# GucciAux.net
KiCad netlist of a schematic drawn in EAGLE
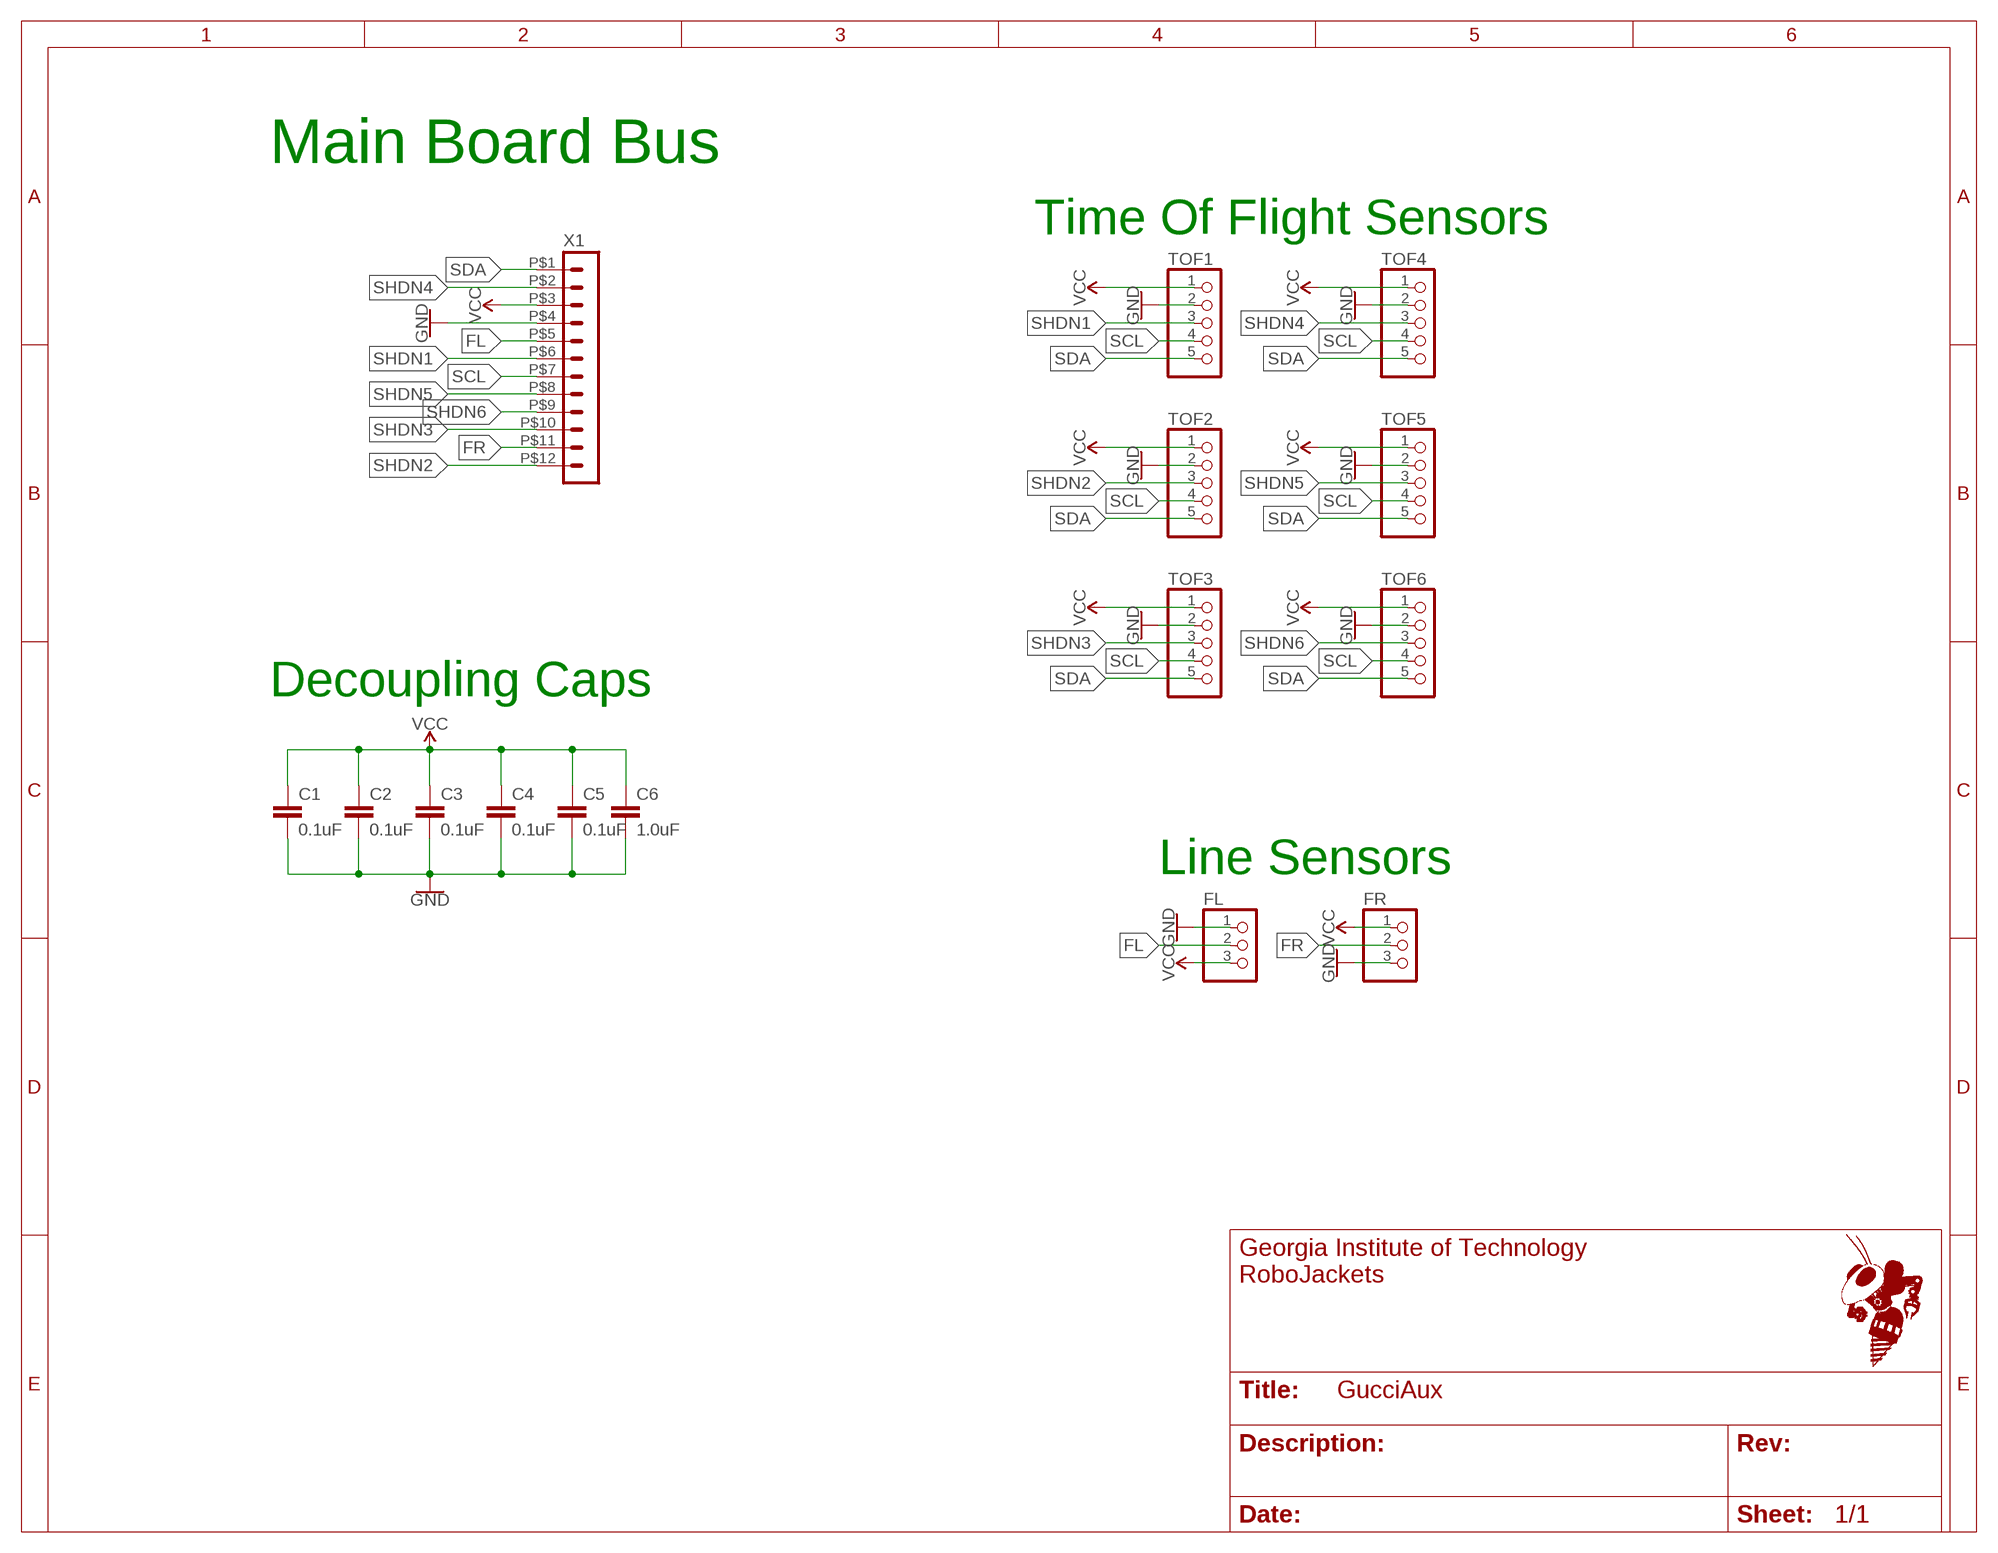
[diagram p0: schematic, sheet 1]

(export (version "E")
  (design (tool "Eeschema 10.0.6"))
  (components
    (comp (ref "C1")
      (value "0.1uF")
      (footprint "eagle-import:0603")
      (libsource (lib "eagle-import") (part "0.1UF-0603-25V-(+80/-20%)"))
    )
    (comp (ref "C2")
      (value "0.1uF")
      (footprint "eagle-import:0603")
      (libsource (lib "eagle-import") (part "0.1UF-0603-25V-(+80/-20%)"))
    )
    (comp (ref "C3")
      (value "0.1uF")
      (footprint "eagle-import:0603")
      (libsource (lib "eagle-import") (part "0.1UF-0603-25V-(+80/-20%)"))
    )
    (comp (ref "C4")
      (value "0.1uF")
      (footprint "eagle-import:0603")
      (libsource (lib "eagle-import") (part "0.1UF-0603-25V-(+80/-20%)"))
    )
    (comp (ref "C5")
      (value "0.1uF")
      (footprint "eagle-import:0603")
      (libsource (lib "eagle-import") (part "0.1UF-0603-25V-(+80/-20%)"))
    )
    (comp (ref "C6")
      (value "1.0uF")
      (footprint "eagle-import:0603")
      (libsource (lib "eagle-import") (part "1.0UF-0603-16V-10%"))
    )
    (comp (ref "FL")
      (value "PINHD-1X3")
      (footprint "eagle-import:1X03")
      (libsource (lib "eagle-import") (part "PINHD-1X3"))
    )
    (comp (ref "FR")
      (value "PINHD-1X3")
      (footprint "eagle-import:1X03")
      (libsource (lib "eagle-import") (part "PINHD-1X3"))
    )
    (comp (ref "TOF1")
      (value "PINHD-1X5")
      (footprint "eagle-import:1X05")
      (libsource (lib "eagle-import") (part "PINHD-1X5"))
    )
    (comp (ref "TOF2")
      (value "PINHD-1X5")
      (footprint "eagle-import:1X05")
      (libsource (lib "eagle-import") (part "PINHD-1X5"))
    )
    (comp (ref "TOF3")
      (value "PINHD-1X5")
      (footprint "eagle-import:1X05")
      (libsource (lib "eagle-import") (part "PINHD-1X5"))
    )
    (comp (ref "TOF4")
      (value "PINHD-1X5")
      (footprint "eagle-import:1X05")
      (libsource (lib "eagle-import") (part "PINHD-1X5"))
    )
    (comp (ref "TOF5")
      (value "PINHD-1X5")
      (footprint "eagle-import:1X05")
      (libsource (lib "eagle-import") (part "PINHD-1X5"))
    )
    (comp (ref "TOF6")
      (value "PINHD-1X5")
      (footprint "eagle-import:1X05")
      (libsource (lib "eagle-import") (part "PINHD-1X5"))
    )
    (comp (ref "X1")
      (value "HEADER_POS12_43045-1212")
      (footprint "eagle-import:43045-1212")
      (libsource (lib "eagle-import") (part "HEADER_POS12_?43045-1212"))
    )
  )
  (nets
    (net (code "1") (name "FL") (class "Default")
      (node (ref "FL") (pin "2") (pinfunction "2_2") (pintype "passive"))
      (node (ref "X1") (pin "P$5") (pinfunction "5_P$5") (pintype "passive"))
    )
    (net (code "2") (name "FR") (class "Default")
      (node (ref "FR") (pin "2") (pinfunction "2_2") (pintype "passive"))
      (node (ref "X1") (pin "P$11") (pinfunction "11_P$11") (pintype "passive"))
    )
    (net (code "3") (name "GND") (class "Default")
      (node (ref "C1") (pin "2") (pinfunction "2_2") (pintype "passive"))
      (node (ref "C2") (pin "2") (pinfunction "2_2") (pintype "passive"))
      (node (ref "C3") (pin "2") (pinfunction "2_2") (pintype "passive"))
      (node (ref "C4") (pin "2") (pinfunction "2_2") (pintype "passive"))
      (node (ref "C5") (pin "2") (pinfunction "2_2") (pintype "passive"))
      (node (ref "C6") (pin "2") (pinfunction "2_2") (pintype "passive"))
      (node (ref "FL") (pin "1") (pinfunction "1_1") (pintype "passive"))
      (node (ref "FR") (pin "3") (pinfunction "3_3") (pintype "passive"))
      (node (ref "TOF1") (pin "2") (pinfunction "2_2") (pintype "passive"))
      (node (ref "TOF2") (pin "2") (pinfunction "2_2") (pintype "passive"))
      (node (ref "TOF3") (pin "2") (pinfunction "2_2") (pintype "passive"))
      (node (ref "TOF4") (pin "2") (pinfunction "2_2") (pintype "passive"))
      (node (ref "TOF5") (pin "2") (pinfunction "2_2") (pintype "passive"))
      (node (ref "TOF6") (pin "2") (pinfunction "2_2") (pintype "passive"))
      (node (ref "X1") (pin "P$4") (pinfunction "4_P$4") (pintype "passive"))
    )
    (net (code "4") (name "SCL") (class "Default")
      (node (ref "TOF1") (pin "4") (pinfunction "4_4") (pintype "passive"))
      (node (ref "TOF2") (pin "4") (pinfunction "4_4") (pintype "passive"))
      (node (ref "TOF3") (pin "4") (pinfunction "4_4") (pintype "passive"))
      (node (ref "TOF4") (pin "4") (pinfunction "4_4") (pintype "passive"))
      (node (ref "TOF5") (pin "4") (pinfunction "4_4") (pintype "passive"))
      (node (ref "TOF6") (pin "4") (pinfunction "4_4") (pintype "passive"))
      (node (ref "X1") (pin "P$7") (pinfunction "7_P$7") (pintype "passive"))
    )
    (net (code "5") (name "SDA") (class "Default")
      (node (ref "TOF1") (pin "5") (pinfunction "5_5") (pintype "passive"))
      (node (ref "TOF2") (pin "5") (pinfunction "5_5") (pintype "passive"))
      (node (ref "TOF3") (pin "5") (pinfunction "5_5") (pintype "passive"))
      (node (ref "TOF4") (pin "5") (pinfunction "5_5") (pintype "passive"))
      (node (ref "TOF5") (pin "5") (pinfunction "5_5") (pintype "passive"))
      (node (ref "TOF6") (pin "5") (pinfunction "5_5") (pintype "passive"))
      (node (ref "X1") (pin "P$1") (pinfunction "1_P$1") (pintype "passive"))
    )
    (net (code "6") (name "SHDN1") (class "Default")
      (node (ref "TOF1") (pin "3") (pinfunction "3_3") (pintype "passive"))
      (node (ref "X1") (pin "P$6") (pinfunction "6_P$6") (pintype "passive"))
    )
    (net (code "7") (name "SHDN2") (class "Default")
      (node (ref "TOF2") (pin "3") (pinfunction "3_3") (pintype "passive"))
      (node (ref "X1") (pin "P$12") (pinfunction "12_P$12") (pintype "passive"))
    )
    (net (code "8") (name "SHDN3") (class "Default")
      (node (ref "TOF3") (pin "3") (pinfunction "3_3") (pintype "passive"))
      (node (ref "X1") (pin "P$10") (pinfunction "10_P$10") (pintype "passive"))
    )
    (net (code "9") (name "SHDN4") (class "Default")
      (node (ref "TOF4") (pin "3") (pinfunction "3_3") (pintype "passive"))
      (node (ref "X1") (pin "P$2") (pinfunction "2_P$2") (pintype "passive"))
    )
    (net (code "10") (name "SHDN5") (class "Default")
      (node (ref "TOF5") (pin "3") (pinfunction "3_3") (pintype "passive"))
      (node (ref "X1") (pin "P$8") (pinfunction "8_P$8") (pintype "passive"))
    )
    (net (code "11") (name "SHDN6") (class "Default")
      (node (ref "TOF6") (pin "3") (pinfunction "3_3") (pintype "passive"))
      (node (ref "X1") (pin "P$9") (pinfunction "9_P$9") (pintype "passive"))
    )
    (net (code "12") (name "VCC") (class "Default")
      (node (ref "C1") (pin "1") (pinfunction "1_1") (pintype "passive"))
      (node (ref "C2") (pin "1") (pinfunction "1_1") (pintype "passive"))
      (node (ref "C3") (pin "1") (pinfunction "1_1") (pintype "passive"))
      (node (ref "C4") (pin "1") (pinfunction "1_1") (pintype "passive"))
      (node (ref "C5") (pin "1") (pinfunction "1_1") (pintype "passive"))
      (node (ref "C6") (pin "1") (pinfunction "1_1") (pintype "passive"))
      (node (ref "FL") (pin "3") (pinfunction "3_3") (pintype "passive"))
      (node (ref "FR") (pin "1") (pinfunction "1_1") (pintype "passive"))
      (node (ref "TOF1") (pin "1") (pinfunction "1_1") (pintype "passive"))
      (node (ref "TOF2") (pin "1") (pinfunction "1_1") (pintype "passive"))
      (node (ref "TOF3") (pin "1") (pinfunction "1_1") (pintype "passive"))
      (node (ref "TOF4") (pin "1") (pinfunction "1_1") (pintype "passive"))
      (node (ref "TOF5") (pin "1") (pinfunction "1_1") (pintype "passive"))
      (node (ref "TOF6") (pin "1") (pinfunction "1_1") (pintype "passive"))
      (node (ref "X1") (pin "P$3") (pinfunction "3_P$3") (pintype "passive"))
    )
  )
)
